# 1608_-_1.net
KiCad netlist of a schematic drawn in Altium Designer
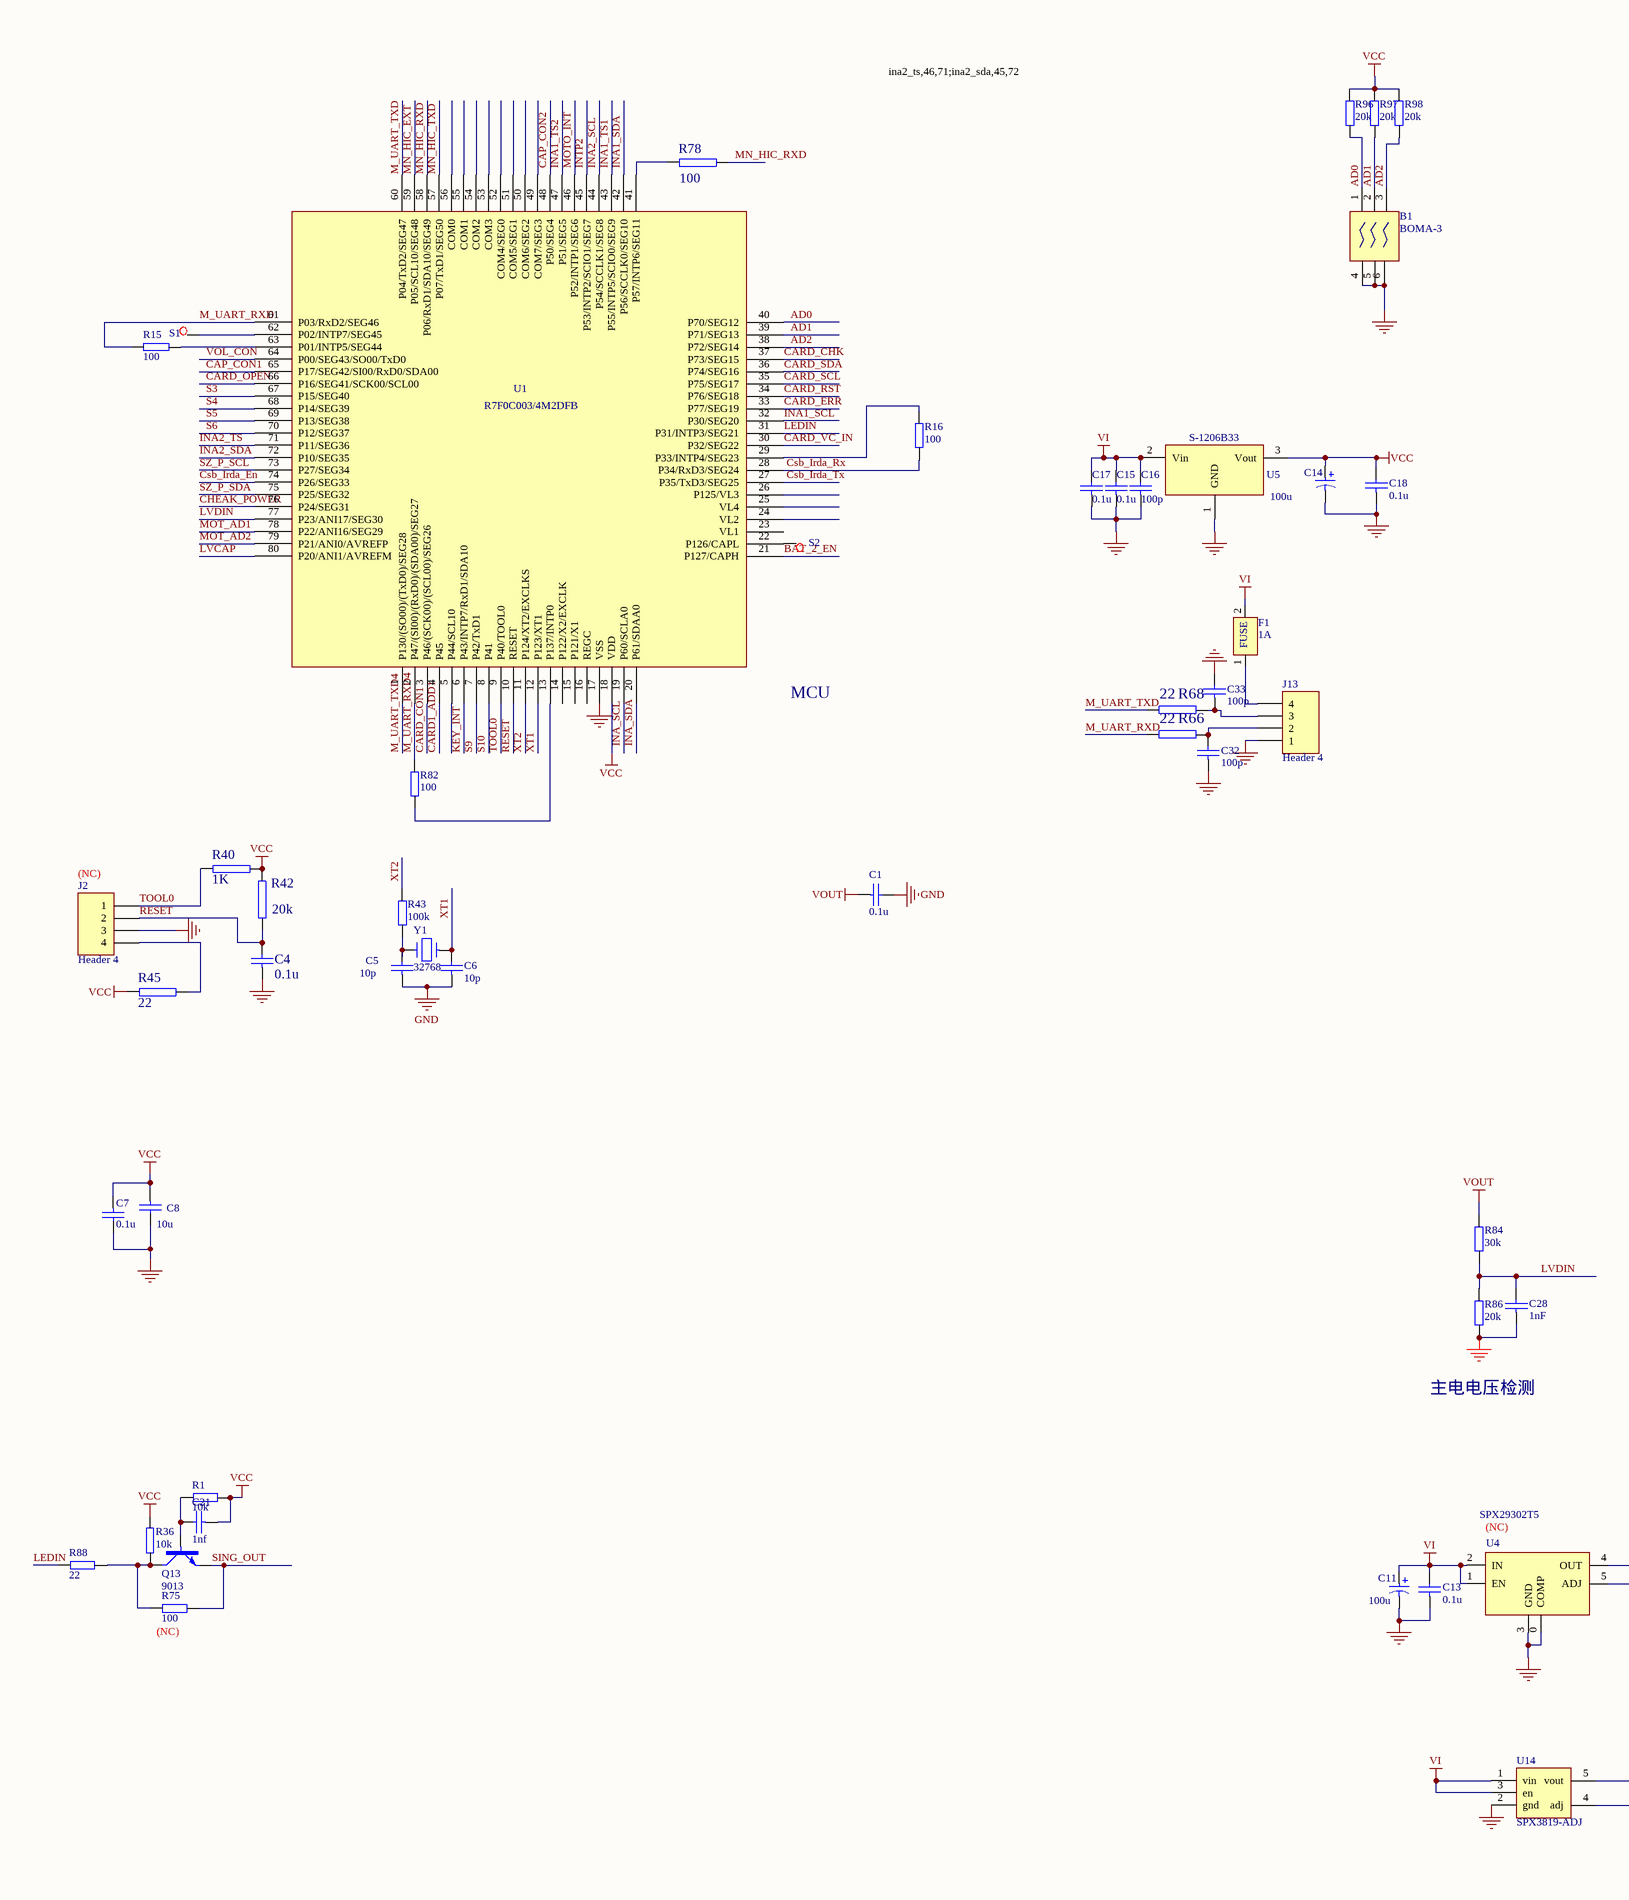
[diagram p0: 1608卡-原理图1.SchDoc, left]
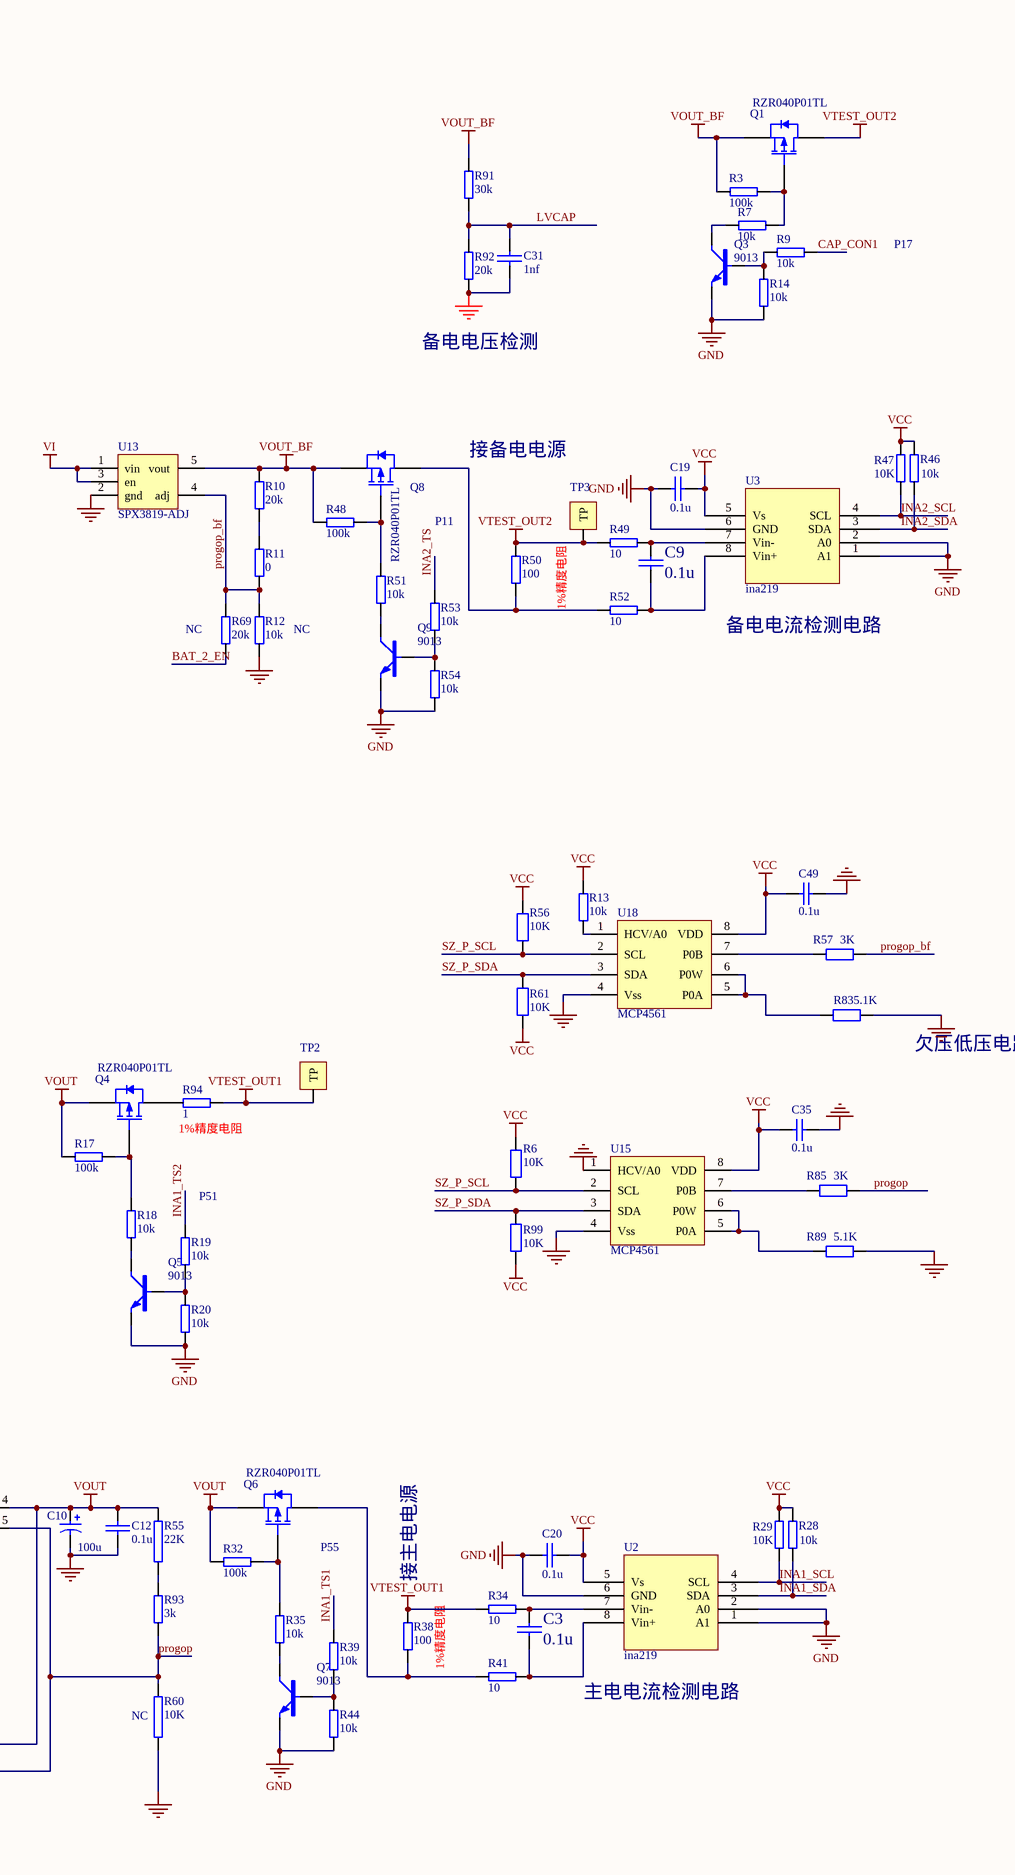
[diagram p1: 1608卡-原理图1.SchDoc, right]

(export (version "E")
  (design (tool "Eeschema 10.0.6"))
  (components
    (comp (ref "B1") (value "BOMA-3") (footprint "BOMA-3") (libsource (lib "chip") (part "BOMA-3")))
    (comp (ref "C1")
      (value "0.1u")
      (footprint "C0603")
      (description "无极性电容")
      (libsource (lib "CBB_Lib_SCH") (part "CAP"))
    )
    (comp (ref "C3") (value "0.1u") (footprint "C0603") (libsource (lib "*") (part "Pro28.tmp_UnNamed_45")))
    (comp (ref "C4")
      (value "0.1u")
      (footprint "C0603")
      (description "Capacitor")
      (libsource (lib "*") (part "CAP"))
    )
    (comp (ref "C5") (value "10p") (footprint "c0603") (libsource (lib "SCH_LIB_WX") (part "CAP1")))
    (comp (ref "C6") (value "10p") (footprint "c0603") (libsource (lib "SCH_LIB_WX") (part "CAP1")))
    (comp (ref "C7")
      (value "0.1u")
      (footprint "C0603")
      (description "无极性电容")
      (libsource (lib "CBB_Lib_SCH") (part "CAP"))
    )
    (comp (ref "C8")
      (value "10u")
      (footprint "C0603")
      (description "无极性电容")
      (libsource (lib "CBB_Lib_SCH") (part "CAP"))
    )
    (comp (ref "C9") (value "0.1u") (footprint "C0603") (libsource (lib "*") (part "Pro28.tmp_UnNamed_45")))
    (comp (ref "C10")
      (value "100u")
      (footprint "3528")
      (description "钽电容")
      (libsource (lib "CBB_Lib_SCH") (part "CAP-POL2"))
    )
    (comp (ref "C11")
      (value "100u")
      (footprint "3528")
      (description "钽电容")
      (libsource (lib "CBB_Lib_SCH") (part "CAP-POL2"))
    )
    (comp (ref "C12")
      (value "0.1u")
      (footprint "C0603")
      (description "无极性电容")
      (libsource (lib "CBB_Lib_SCH") (part "CAP"))
    )
    (comp (ref "C13")
      (value "0.1u")
      (footprint "C0603")
      (description "无极性电容")
      (libsource (lib "CBB_Lib_SCH") (part "CAP"))
    )
    (comp (ref "C14")
      (value "100u")
      (footprint "3528")
      (description "钽电容")
      (libsource (lib "CBB_Lib_SCH") (part "CAP-POL2"))
    )
    (comp (ref "C15")
      (value "0.1u")
      (footprint "C0603")
      (description "无极性电容")
      (libsource (lib "CBB_Lib_SCH") (part "CAP"))
    )
    (comp (ref "C16")
      (value "100p")
      (footprint "C0603")
      (description "无极性电容")
      (libsource (lib "CBB_Lib_SCH") (part "CAP"))
    )
    (comp (ref "C17")
      (value "0.1u")
      (footprint "C0603")
      (description "无极性电容")
      (libsource (lib "CBB_Lib_SCH") (part "CAP"))
    )
    (comp (ref "C18")
      (value "0.1u")
      (footprint "C0603")
      (description "无极性电容")
      (libsource (lib "CBB_Lib_SCH") (part "CAP"))
    )
    (comp (ref "C19")
      (value "0.1u")
      (footprint "C0603")
      (description "无极性电容")
      (libsource (lib "CBB_Lib_SCH") (part "CAP"))
    )
    (comp (ref "C20")
      (value "0.1u")
      (footprint "C0603")
      (description "无极性电容")
      (libsource (lib "CBB_Lib_SCH") (part "CAP"))
    )
    (comp (ref "C21")
      (value "1nf")
      (footprint "C0603")
      (description "无极性电容")
      (libsource (lib "CBB_Lib_SCH") (part "CAP"))
    )
    (comp (ref "C28")
      (value "1nF")
      (footprint "C0603")
      (description "无极性电容")
      (libsource (lib "CBB_Lib_SCH") (part "CAP"))
    )
    (comp (ref "C31")
      (value "1nf")
      (footprint "C0603")
      (description "无极性电容")
      (libsource (lib "CBB_Lib_SCH") (part "CAP"))
    )
    (comp (ref "C32")
      (value "100p")
      (footprint "C0603")
      (description "无极性电容")
      (libsource (lib "CBB_Lib_SCH") (part "CAP"))
    )
    (comp (ref "C33")
      (value "100p")
      (footprint "C0603")
      (description "无极性电容")
      (libsource (lib "CBB_Lib_SCH") (part "CAP"))
    )
    (comp (ref "C35")
      (value "0.1u")
      (footprint "c0603")
      (description "Capacitor")
      (fields (field (name "PUBLISHER") "Altium Limited"))
      (libsource (lib "Miscellaneous Devices") (part "Cap"))
    )
    (comp (ref "C49")
      (value "0.1u")
      (footprint "c0603")
      (description "Capacitor")
      (fields (field (name "PUBLISHER") "Altium Limited"))
      (libsource (lib "Miscellaneous Devices") (part "Cap"))
    )
    (comp (ref "F1") (value "1A") (footprint "R1206") (libsource (lib "chip") (part "FUSE")))
    (comp (ref "J2")
      (value "Header 4")
      (footprint "HDR1X4")
      (description "Header, 4-Pin")
      (fields (field (name "PUBLISHER") "Altium Limited"))
      (libsource (lib "") (part "Header 4_1"))
    )
    (comp (ref "J13")
      (value "Header 4")
      (footprint "HDX4")
      (description "Header, 4-Pin")
      (fields (field (name "PUBLISHER") "Altium Limited"))
      (libsource (lib "Miscellaneous Connectors") (part "Header 4"))
    )
    (comp (ref "Q1")
      (value "RZR040P01TL")
      (footprint "SOT-23-MOS")
      (description "P-channel  MOSFET")
      (libsource (lib "CBB_Lib_SCH") (part "MOS-P"))
    )
    (comp (ref "Q3")
      (value "9013")
      (footprint "SOT-23-TRAN")
      (description "NPN Transistor")
      (libsource (lib "CBB_Lib_SCH") (part "NPN-S"))
    )
    (comp (ref "Q4")
      (value "RZR040P01TL")
      (footprint "SOT-23-MOS")
      (description "P-channel  MOSFET")
      (libsource (lib "CBB_Lib_SCH") (part "MOS-P"))
    )
    (comp (ref "Q5")
      (value "9013")
      (footprint "SOT-23-TRAN")
      (description "NPN Transistor")
      (libsource (lib "CBB_Lib_SCH") (part "NPN-S"))
    )
    (comp (ref "Q6")
      (value "RZR040P01TL")
      (footprint "SOT-23-MOS")
      (description "P-channel  MOSFET")
      (libsource (lib "CBB_Lib_SCH") (part "MOS-P"))
    )
    (comp (ref "Q7")
      (value "9013")
      (footprint "SOT-23-TRAN")
      (description "NPN Transistor")
      (libsource (lib "CBB_Lib_SCH") (part "NPN-S"))
    )
    (comp (ref "Q8")
      (value "RZR040P01TL")
      (footprint "SOT-23-MOS")
      (description "P-channel  MOSFET")
      (libsource (lib "CBB_Lib_SCH") (part "MOS-P"))
    )
    (comp (ref "Q9")
      (value "9013")
      (footprint "SOT-23-TRAN")
      (description "NPN Transistor")
      (libsource (lib "CBB_Lib_SCH") (part "NPN-S"))
    )
    (comp (ref "Q13")
      (value "9013")
      (footprint "CBB_Lib_PCB:SOT-23-TRAN")
      (description "NPN Transistor")
      (libsource (lib "CBB_Lib_SCH") (part "NPN-S"))
    )
    (comp (ref "R1") (value "10k") (footprint "R0603") (libsource (lib "CBB_linshi_SCH") (part "RES  PASS")))
    (comp (ref "R3") (value "100k") (footprint "R0603") (libsource (lib "CBB_Lib_SCH") (part "RES")))
    (comp (ref "R6")
      (value "10K")
      (footprint "R0603")
      (description "Resistor")
      (fields (field (name "PUBLISHER") "Altium Limited"))
      (libsource (lib "Miscellaneous Devices") (part "Res2"))
    )
    (comp (ref "R7") (value "10k") (footprint "R0603") (libsource (lib "CBB_Lib_SCH") (part "RES")))
    (comp (ref "R9") (value "10k") (footprint "R0603") (libsource (lib "CBB_Lib_SCH") (part "RES")))
    (comp (ref "R10") (value "20k") (footprint "R0603") (libsource (lib "CBB_Lib_SCH") (part "RES")))
    (comp (ref "R11") (value "0") (footprint "R0603") (libsource (lib "CBB_Lib_SCH") (part "RES")))
    (comp (ref "R12") (value "10k") (footprint "R0603") (libsource (lib "CBB_Lib_SCH") (part "RES")))
    (comp (ref "R13") (value "10k") (footprint "R0603") (libsource (lib "CBB_Lib_SCH") (part "RES")))
    (comp (ref "R14") (value "10k") (footprint "R0603") (libsource (lib "CBB_Lib_SCH") (part "RES")))
    (comp (ref "R15") (value "100") (footprint "r0603") (libsource (lib "SCH_LIB_WX") (part "RES")))
    (comp (ref "R16") (value "100") (footprint "R0603") (libsource (lib "Devices") (part "RES")))
    (comp (ref "R17") (value "100k") (footprint "R0603") (libsource (lib "CBB_Lib_SCH") (part "RES")))
    (comp (ref "R18") (value "10k") (footprint "R0603") (libsource (lib "CBB_Lib_SCH") (part "RES")))
    (comp (ref "R19") (value "10k") (footprint "R0603") (libsource (lib "CBB_Lib_SCH") (part "RES")))
    (comp (ref "R20") (value "10k") (footprint "R0603") (libsource (lib "CBB_Lib_SCH") (part "RES")))
    (comp (ref "R28") (value "10k") (footprint "R0603") (libsource (lib "Int_Lib_WX") (part "RES")))
    (comp (ref "R29") (value "10K") (footprint "R0603") (libsource (lib "Int_Lib_WX") (part "RES")))
    (comp (ref "R32") (value "100k") (footprint "R0603") (libsource (lib "CBB_Lib_SCH") (part "RES")))
    (comp (ref "R34") (value "10") (footprint "R0603") (libsource (lib "CBB_Lib_SCH") (part "RES")))
    (comp (ref "R35") (value "10k") (footprint "R0603") (libsource (lib "CBB_Lib_SCH") (part "RES")))
    (comp (ref "R36") (value "10k") (footprint "R0603") (libsource (lib "CBB_linshi_SCH") (part "RES  PASS")))
    (comp (ref "R38") (value "100") (footprint "R1206") (libsource (lib "CBB_Lib_SCH") (part "RES")))
    (comp (ref "R39") (value "10k") (footprint "R0603") (libsource (lib "CBB_Lib_SCH") (part "RES")))
    (comp (ref "R40") (value "1K") (footprint "R0603") (libsource (lib "*") (part "RES11")))
    (comp (ref "R41") (value "10") (footprint "R0603") (libsource (lib "CBB_Lib_SCH") (part "RES")))
    (comp (ref "R42") (value "20k") (footprint "R0603") (libsource (lib "*") (part "RES11")))
    (comp (ref "R43") (value "100k") (footprint "r0603") (libsource (lib "SCH_LIB_WX") (part "RES")))
    (comp (ref "R44") (value "10k") (footprint "R0603") (libsource (lib "CBB_Lib_SCH") (part "RES")))
    (comp (ref "R45") (value "22") (footprint "R0603") (libsource (lib "*") (part "RES11")))
    (comp (ref "R46") (value "10k") (footprint "R0603") (libsource (lib "Int_Lib_WX") (part "RES")))
    (comp (ref "R47") (value "10K") (footprint "R0603") (libsource (lib "Int_Lib_WX") (part "RES")))
    (comp (ref "R48") (value "100k") (footprint "R0603") (libsource (lib "CBB_Lib_SCH") (part "RES")))
    (comp (ref "R49") (value "10") (footprint "R0603") (libsource (lib "CBB_Lib_SCH") (part "RES")))
    (comp (ref "R50") (value "100") (footprint "R1206") (libsource (lib "CBB_Lib_SCH") (part "RES")))
    (comp (ref "R51") (value "10k") (footprint "R0603") (libsource (lib "CBB_Lib_SCH") (part "RES")))
    (comp (ref "R52") (value "10") (footprint "R0603") (libsource (lib "CBB_Lib_SCH") (part "RES")))
    (comp (ref "R53") (value "10k") (footprint "R0603") (libsource (lib "CBB_Lib_SCH") (part "RES")))
    (comp (ref "R54") (value "10k") (footprint "R0603") (libsource (lib "CBB_Lib_SCH") (part "RES")))
    (comp (ref "R55") (value "22K") (footprint "R0603") (libsource (lib "*") (part "RES2")))
    (comp (ref "R56")
      (value "10K")
      (footprint "R0603")
      (description "Resistor")
      (fields (field (name "PUBLISHER") "Altium Limited"))
      (libsource (lib "Miscellaneous Devices") (part "Res2"))
    )
    (comp (ref "R57")
      (value "3K")
      (footprint "R0603")
      (description "Resistor")
      (fields (field (name "PUBLISHER") "Altium Limited"))
      (libsource (lib "") (part "Res2_1"))
    )
    (comp (ref "R60") (value "10K") (footprint "R0603") (libsource (lib "*") (part "RES2")))
    (comp (ref "R61")
      (value "10K")
      (footprint "R0603")
      (description "Resistor")
      (fields (field (name "PUBLISHER") "Altium Limited"))
      (libsource (lib "Miscellaneous Devices") (part "Res2"))
    )
    (comp (ref "R66") (value "22") (footprint "R0603") (libsource (lib "PCB_Project1_1") (part "RES2")))
    (comp (ref "R68") (value "22") (footprint "R0603") (libsource (lib "PCB_Project1_1") (part "RES2")))
    (comp (ref "R69") (value "20k") (footprint "R0603") (libsource (lib "CBB_Lib_SCH") (part "RES")))
    (comp (ref "R75") (value "100") (footprint "R0603") (libsource (lib "") (part "RES  PASS_1")))
    (comp (ref "R78") (value "100") (footprint "R0603") (libsource (lib "*") (part "RES11")))
    (comp (ref "R82") (value "100") (footprint "R0603") (libsource (lib "Devices") (part "RES")))
    (comp (ref "R83")
      (value "5.1K")
      (footprint "R0603")
      (description "Resistor")
      (fields (field (name "PUBLISHER") "Altium Limited"))
      (libsource (lib "") (part "Res2_1"))
    )
    (comp (ref "R84") (value "30k") (footprint "R0603") (libsource (lib "CBB_Lib_SCH") (part "RES")))
    (comp (ref "R85")
      (value "3K")
      (footprint "R0603")
      (description "Resistor")
      (fields (field (name "PUBLISHER") "Altium Limited"))
      (libsource (lib "") (part "Res2_1"))
    )
    (comp (ref "R86") (value "20k") (footprint "R0603") (libsource (lib "CBB_Lib_SCH") (part "RES")))
    (comp (ref "R88") (value "22") (footprint "R0603") (libsource (lib "CBB_linshi_SCH") (part "RES  PASS")))
    (comp (ref "R89")
      (value "5.1K")
      (footprint "R0603")
      (description "Resistor")
      (fields (field (name "PUBLISHER") "Altium Limited"))
      (libsource (lib "") (part "Res2_1"))
    )
    (comp (ref "R91") (value "30k") (footprint "R0603") (libsource (lib "CBB_Lib_SCH") (part "RES")))
    (comp (ref "R92") (value "20k") (footprint "R0603") (libsource (lib "CBB_Lib_SCH") (part "RES")))
    (comp (ref "R93") (value "3k") (footprint "R0603") (libsource (lib "CBB_Lib_SCH") (part "RES")))
    (comp (ref "R94") (value "1") (footprint "R1206") (libsource (lib "CBB_Lib_SCH") (part "RES")))
    (comp (ref "R96") (value "20k") (footprint "R0603") (libsource (lib "CBB_Lib_SCH") (part "RES")))
    (comp (ref "R97") (value "20k") (footprint "R0603") (libsource (lib "CBB_Lib_SCH") (part "RES")))
    (comp (ref "R98") (value "20k") (footprint "R0603") (libsource (lib "CBB_Lib_SCH") (part "RES")))
    (comp (ref "R99")
      (value "10K")
      (footprint "R0603")
      (description "Resistor")
      (fields (field (name "PUBLISHER") "Altium Limited"))
      (libsource (lib "Miscellaneous Devices") (part "Res2"))
    )
    (comp (ref "S1")
      (value "Test Point  PASS")
      (footprint "TP_S")
      (description "测试点")
      (libsource (lib "CBB_Lib_SCH") (part "Test Point  PASS"))
    )
    (comp (ref "S2")
      (value "Test Point  PASS")
      (footprint "TP_S")
      (description "测试点")
      (libsource (lib "CBB_Lib_SCH") (part "Test Point  PASS"))
    )
    (comp (ref "TP2") (value "TP") (footprint "TEST_PAD") (libsource (lib "chip") (part "TP")))
    (comp (ref "TP3") (value "TP") (footprint "TEST_PAD") (libsource (lib "chip") (part "TP")))
    (comp (ref "U1")
      (value "R7F0C003/4M2DFB")
      (footprint "MSP437QFP80")
      (libsource (lib "Schlib1") (part "R7F0C003/4M2DFB"))
    )
    (comp (ref "U2") (value "ina219") (footprint "SO-8") (libsource (lib "Schlib1") (part "Component_2")))
    (comp (ref "U3") (value "ina219") (footprint "SO-8") (libsource (lib "Schlib1") (part "Component_2")))
    (comp (ref "U4")
      (value "SPX29302T5")
      (footprint "TO-263-5")
      (fields (field (name "PUBLISHER") "Altium Limited"))
      (libsource (lib "SCH_LIB_WX") (part "SPX29302T5"))
    )
    (comp (ref "U5") (value "S-1206B33") (footprint "SOT-89") (libsource (lib "*") (part "VOLTRER1")))
    (comp (ref "U13")
      (value "SPX3819-ADJ")
      (footprint "SOT23-5")
      (libsource (lib "chip") (part "SPX3819-ADJ"))
    )
    (comp (ref "U14")
      (value "SPX3819-ADJ")
      (footprint "SOT23-5")
      (libsource (lib "chip") (part "SPX3819-ADJ"))
    )
    (comp (ref "U15") (value "MCP4561") (footprint "MSOP") (libsource (lib "ultra") (part "MCP4561")))
    (comp (ref "U18") (value "MCP4561") (footprint "MSOP") (libsource (lib "ultra") (part "MCP4561")))
    (comp (ref "Y1")
      (value "32768")
      (footprint "XTAL-2S")
      (description "晶振,2PIN")
      (libsource (lib "CBB_Lib_SCH") (part "XTAL1"))
    )
  )
  (nets
    (net (code "1") (name "/AD0") (class "Default")
      (node (ref "B1") (pin "1") (pinfunction "vout_1") (pintype "passive"))
      (node (ref "R96") (pin "1") (pintype "passive"))
      (node (ref "U1") (pin "40") (pinfunction "P70/SEG12_40") (pintype "passive"))
    )
    (net (code "2") (name "/AD1") (class "Default")
      (node (ref "B1") (pin "2") (pinfunction "vout_2") (pintype "passive"))
      (node (ref "R97") (pin "1") (pintype "passive"))
      (node (ref "U1") (pin "39") (pinfunction "P71/SEG13_39") (pintype "passive"))
    )
    (net (code "3") (name "/AD2") (class "Default")
      (node (ref "B1") (pin "3") (pinfunction "vout_3") (pintype "passive"))
      (node (ref "R98") (pin "1") (pintype "passive"))
      (node (ref "U1") (pin "38") (pinfunction "P72/SEG14_38") (pintype "passive"))
    )
    (net (code "4") (name "/BAT_2_EN") (class "Default")
      (node (ref "R69") (pin "2") (pintype "passive"))
      (node (ref "U1") (pin "21") (pinfunction "P127/CAPH_21") (pintype "passive"))
    )
    (net (code "5") (name "/CAP_CON1") (class "Default")
      (node (ref "R9") (pin "2") (pintype "passive"))
      (node (ref "U1") (pin "65") (pinfunction "P17/SEG42/SI00/RxD0/SDA00_65") (pintype "passive"))
    )
    (net (code "6") (name "/CAP_CON2") (class "Default")
      (node (ref "U1") (pin "48") (pinfunction "P50/SEG4_48") (pintype "passive"))
    )
    (net (code "7") (name "/CARD1_ADD1") (class "Default")
      (node (ref "U1") (pin "4") (pinfunction "P45_4") (pintype "passive"))
    )
    (net (code "8") (name "/CARD_CHK") (class "Default")
      (node (ref "U1") (pin "37") (pinfunction "P73/SEG15_37") (pintype "passive"))
    )
    (net (code "9") (name "/CARD_CON1") (class "Default")
      (node (ref "U1") (pin "3") (pinfunction "P46/(SCK00)/(SCL00)/SEG26_3") (pintype "passive"))
    )
    (net (code "10") (name "/CARD_ERR") (class "Default")
      (node (ref "U1") (pin "33") (pinfunction "P77/SEG19_33") (pintype "passive"))
    )
    (net (code "11") (name "/CARD_OPEN") (class "Default")
      (node (ref "U1") (pin "66") (pinfunction "P16/SEG41/SCK00/SCL00_66") (pintype "passive"))
    )
    (net (code "12") (name "/CARD_RST") (class "Default")
      (node (ref "U1") (pin "34") (pinfunction "P76/SEG18_34") (pintype "passive"))
    )
    (net (code "13") (name "/CARD_SCL") (class "Default")
      (node (ref "U1") (pin "35") (pinfunction "P75/SEG17_35") (pintype "passive"))
    )
    (net (code "14") (name "/CARD_SDA") (class "Default")
      (node (ref "U1") (pin "36") (pinfunction "P74/SEG16_36") (pintype "passive"))
    )
    (net (code "15") (name "/CARD_VC_IN") (class "Default")
      (node (ref "U1") (pin "30") (pinfunction "P32/SEG22_30") (pintype "passive"))
    )
    (net (code "16") (name "/CHEAK_POWER") (class "Default")
      (node (ref "U1") (pin "76") (pinfunction "P24/SEG31_76") (pintype "passive"))
    )
    (net (code "17") (name "/Csb_Irda_En") (class "Default")
      (node (ref "U1") (pin "74") (pinfunction "P26/SEG33_74") (pintype "passive"))
    )
    (net (code "18") (name "/Csb_Irda_Rx") (class "Default")
      (node (ref "R16") (pin "1") (pintype "passive"))
      (node (ref "U1") (pin "28") (pinfunction "P34/RxD3/SEG24_28") (pintype "passive"))
    )
    (net (code "19") (name "/Csb_Irda_Tx") (class "Default")
      (node (ref "U1") (pin "27") (pinfunction "P35/TxD3/SEG25_27") (pintype "passive"))
    )
    (net (code "20") (name "/INA1_SCL") (class "Default")
      (node (ref "R29") (pin "1") (pintype "passive"))
      (node (ref "U1") (pin "32") (pinfunction "P30/SEG20_32") (pintype "passive"))
      (node (ref "U2") (pin "4") (pinfunction "SCL_4") (pintype "passive"))
    )
    (net (code "21") (name "/INA1_SDA") (class "Default")
      (node (ref "R28") (pin "1") (pintype "passive"))
      (node (ref "U1") (pin "42") (pinfunction "P56/SCCLK0/SEG10_42") (pintype "passive"))
      (node (ref "U2") (pin "3") (pinfunction "SDA_3") (pintype "passive"))
    )
    (net (code "22") (name "/INA1_TS1") (class "Default")
      (node (ref "R39") (pin "2") (pintype "passive"))
      (node (ref "U1") (pin "43") (pinfunction "P55/INTP5/SCIO0/SEG9_43") (pintype "passive"))
    )
    (net (code "23") (name "/INA1_TS2") (class "Default")
      (node (ref "R19") (pin "2") (pintype "passive"))
      (node (ref "U1") (pin "47") (pinfunction "P51/SEG5_47") (pintype "passive"))
    )
    (net (code "24") (name "/INA2_SCL") (class "Default")
      (node (ref "R47") (pin "1") (pintype "passive"))
      (node (ref "U1") (pin "44") (pinfunction "P54/SCCLK1/SEG8_44") (pintype "passive"))
      (node (ref "U3") (pin "4") (pinfunction "SCL_4") (pintype "passive"))
    )
    (net (code "25") (name "/INA2_SDA") (class "Default")
      (node (ref "R46") (pin "1") (pintype "passive"))
      (node (ref "U1") (pin "72") (pinfunction "P10/SEG35_72") (pintype "passive"))
      (node (ref "U3") (pin "3") (pinfunction "SDA_3") (pintype "passive"))
    )
    (net (code "26") (name "/INA2_TS") (class "Default")
      (node (ref "R53") (pin "2") (pintype "passive"))
      (node (ref "U1") (pin "71") (pinfunction "P11/SEG36_71") (pintype "passive"))
    )
    (net (code "27") (name "/INA_SCL") (class "Default")
      (node (ref "U1") (pin "19") (pinfunction "P60/SCLA0_19") (pintype "passive"))
    )
    (net (code "28") (name "/INA_SDA") (class "Default")
      (node (ref "U1") (pin "20") (pinfunction "P61/SDAA0_20") (pintype "passive"))
    )
    (net (code "29") (name "/INTP2") (class "Default")
      (node (ref "U1") (pin "45") (pinfunction "P53/INTP2/SCIO1/SEG7_45") (pintype "passive"))
    )
    (net (code "30") (name "/KEY_INT") (class "Default")
      (node (ref "U1") (pin "6") (pinfunction "P43/INTP7/RxD1/SDA10_6") (pintype "passive"))
    )
    (net (code "31") (name "/LEDIN") (class "Default")
      (node (ref "R88") (pin "1") (pintype "passive"))
      (node (ref "U1") (pin "31") (pinfunction "P31/INTP3/SEG21_31") (pintype "passive"))
    )
    (net (code "32") (name "/LVCAP") (class "Default")
      (node (ref "C31") (pin "2") (pintype "passive"))
      (node (ref "R91") (pin "2") (pintype "passive"))
      (node (ref "R92") (pin "1") (pintype "passive"))
      (node (ref "U1") (pin "80") (pinfunction "P20/ANI1/AVREFM_80") (pintype "passive"))
    )
    (net (code "33") (name "/LVDIN") (class "Default")
      (node (ref "C28") (pin "2") (pintype "passive"))
      (node (ref "R84") (pin "2") (pintype "passive"))
      (node (ref "R86") (pin "1") (pintype "passive"))
      (node (ref "U1") (pin "77") (pinfunction "P23/ANI17/SEG30_77") (pintype "passive"))
    )
    (net (code "34") (name "/MN_HIC_EXT") (class "Default")
      (node (ref "U1") (pin "59") (pinfunction "P05/SCL10/SEG48_59") (pintype "passive"))
    )
    (net (code "35") (name "/MN_HIC_RXD") (class "Default")
      (node (ref "R78") (pin "2") (pinfunction "2_2") (pintype "passive"))
      (node (ref "U1") (pin "58") (pinfunction "P06/RxD1/SDA10/SEG49_58") (pintype "passive"))
    )
    (net (code "36") (name "/MN_HIC_TXD") (class "Default")
      (node (ref "U1") (pin "57") (pinfunction "P07/TxD1/SEG50_57") (pintype "passive"))
    )
    (net (code "37") (name "/MOTO_INT") (class "Default")
      (node (ref "U1") (pin "46") (pinfunction "P52/INTP1/SEG6_46") (pintype "passive"))
    )
    (net (code "38") (name "/MOT_AD1") (class "Default")
      (node (ref "U1") (pin "78") (pinfunction "P22/ANI16/SEG29_78") (pintype "passive"))
    )
    (net (code "39") (name "/MOT_AD2") (class "Default")
      (node (ref "U1") (pin "79") (pinfunction "P21/ANI0/AVREFP_79") (pintype "passive"))
    )
    (net (code "40") (name "/M_UART_RXD") (class "Default")
      (node (ref "R15") (pin "2") (pintype "passive"))
      (node (ref "R66") (pin "2") (pinfunction "2_2") (pintype "passive"))
      (node (ref "U1") (pin "61") (pinfunction "P03/RxD2/SEG46_61") (pintype "passive"))
    )
    (net (code "41") (name "/M_UART_RXD4") (class "Default")
      (node (ref "R82") (pin "2") (pintype "passive"))
      (node (ref "U1") (pin "2") (pinfunction "P47/(SI00)/(RxD0)/(SDA00)/SEG27_2") (pintype "passive"))
    )
    (net (code "42") (name "/M_UART_TXD") (class "Default")
      (node (ref "R68") (pin "2") (pinfunction "2_2") (pintype "passive"))
      (node (ref "U1") (pin "60") (pinfunction "P04/TxD2/SEG47_60") (pintype "passive"))
    )
    (net (code "43") (name "/M_UART_TXD4") (class "Default")
      (node (ref "U1") (pin "1") (pinfunction "P130/(SO00)/(TxD0)/SEG28_1") (pintype "passive"))
    )
    (net (code "44") (name "/RESET") (class "Default")
      (node (ref "C4") (pin "2") (pinfunction "2_2") (pintype "passive"))
      (node (ref "J2") (pin "2") (pinfunction "2_2") (pintype "passive"))
      (node (ref "R42") (pin "2") (pinfunction "2_2") (pintype "passive"))
      (node (ref "U1") (pin "10") (pinfunction "RESET_10") (pintype "passive"))
    )
    (net (code "45") (name "/S3") (class "Default")
      (node (ref "U1") (pin "67") (pinfunction "P15/SEG40_67") (pintype "passive"))
    )
    (net (code "46") (name "/S4") (class "Default")
      (node (ref "U1") (pin "68") (pinfunction "P14/SEG39_68") (pintype "passive"))
    )
    (net (code "47") (name "/S5") (class "Default")
      (node (ref "U1") (pin "69") (pinfunction "P13/SEG38_69") (pintype "passive"))
    )
    (net (code "48") (name "/S6") (class "Default")
      (node (ref "U1") (pin "70") (pinfunction "P12/SEG37_70") (pintype "passive"))
    )
    (net (code "49") (name "/S9") (class "Default")
      (node (ref "U1") (pin "7") (pinfunction "P42/TxD1_7") (pintype "passive"))
    )
    (net (code "50") (name "/S10") (class "Default")
      (node (ref "U1") (pin "8") (pinfunction "P41_8") (pintype "passive"))
    )
    (net (code "51") (name "/SING_OUT") (class "Default")
      (node (ref "Q13") (pin "E") (pinfunction "E_E") (pintype "passive"))
      (node (ref "R75") (pin "1") (pintype "passive"))
    )
    (net (code "52") (name "/SZ_P_SCL") (class "Default")
      (node (ref "R56") (pin "2") (pinfunction "2_2") (pintype "passive"))
      (node (ref "R6") (pin "2") (pinfunction "2_2") (pintype "passive"))
      (node (ref "U1") (pin "73") (pinfunction "P27/SEG34_73") (pintype "passive"))
      (node (ref "U15") (pin "2") (pinfunction "SCL_2") (pintype "passive"))
      (node (ref "U18") (pin "2") (pinfunction "SCL_2") (pintype "passive"))
    )
    (net (code "53") (name "/SZ_P_SDA") (class "Default")
      (node (ref "R61") (pin "1") (pinfunction "1_1") (pintype "passive"))
      (node (ref "R99") (pin "1") (pinfunction "1_1") (pintype "passive"))
      (node (ref "U1") (pin "75") (pinfunction "P25/SEG32_75") (pintype "passive"))
      (node (ref "U15") (pin "3") (pinfunction "SDA_3") (pintype "passive"))
      (node (ref "U18") (pin "3") (pinfunction "SDA_3") (pintype "passive"))
    )
    (net (code "54") (name "/TOOL0") (class "Default")
      (node (ref "J2") (pin "1") (pinfunction "1_1") (pintype "passive"))
      (node (ref "R40") (pin "1") (pinfunction "1_1") (pintype "passive"))
      (node (ref "U1") (pin "9") (pinfunction "P40/TOOL0_9") (pintype "passive"))
    )
    (net (code "55") (name "/VOL_CON") (class "Default")
      (node (ref "U1") (pin "64") (pinfunction "P00/SEG43/SO00/TxD0_64") (pintype "passive"))
    )
    (net (code "56") (name "/XT1") (class "Default")
      (node (ref "C6") (pin "2") (pintype "passive"))
      (node (ref "U1") (pin "12") (pinfunction "P123/XT1_12") (pintype "passive"))
      (node (ref "Y1") (pin "1") (pinfunction "1_1") (pintype "passive"))
    )
    (net (code "57") (name "/XT2") (class "Default")
      (node (ref "R43") (pin "2") (pintype "passive"))
      (node (ref "U1") (pin "11") (pinfunction "P124/XT2/EXCLKS_11") (pintype "passive"))
    )
    (net (code "58") (name "/progop") (class "Default")
      (node (ref "R60") (pin "1") (pintype "passive"))
      (node (ref "R85") (pin "1") (pinfunction "1_1") (pintype "passive"))
      (node (ref "R93") (pin "2") (pintype "passive"))
      (node (ref "U14") (pin "4") (pinfunction "adj_4") (pintype "passive"))
      (node (ref "U4") (pin "5") (pinfunction "ADJ_5") (pintype "passive"))
    )
    (net (code "59") (name "/progop_bf") (class "Default")
      (node (ref "R11") (pin "1") (pintype "passive"))
      (node (ref "R12") (pin "2") (pintype "passive"))
      (node (ref "R57") (pin "1") (pinfunction "1_1") (pintype "passive"))
      (node (ref "R69") (pin "1") (pintype "passive"))
      (node (ref "U13") (pin "4") (pinfunction "adj_4") (pintype "passive"))
    )
    (net (code "60") (name "GND") (class "Default")
      (node (ref "B1") (pin "4") (pinfunction "vout_4") (pintype "passive"))
      (node (ref "B1") (pin "5") (pinfunction "vout_5") (pintype "passive"))
      (node (ref "B1") (pin "6") (pinfunction "vout_6") (pintype "passive"))
      (node (ref "C1") (pin "2") (pintype "passive"))
      (node (ref "C10") (pin "2") (pinfunction "2_2") (pintype "passive"))
      (node (ref "C11") (pin "2") (pinfunction "2_2") (pintype "passive"))
      (node (ref "C12") (pin "1") (pintype "passive"))
      (node (ref "C13") (pin "1") (pintype "passive"))
      (node (ref "C14") (pin "2") (pinfunction "2_2") (pintype "passive"))
      (node (ref "C15") (pin "1") (pintype "passive"))
      (node (ref "C16") (pin "1") (pintype "passive"))
      (node (ref "C17") (pin "1") (pintype "passive"))
      (node (ref "C18") (pin "1") (pintype "passive"))
      (node (ref "C19") (pin "1") (pintype "passive"))
      (node (ref "C20") (pin "1") (pintype "passive"))
      (node (ref "C28") (pin "1") (pintype "passive"))
      (node (ref "C31") (pin "1") (pintype "passive"))
      (node (ref "C32") (pin "1") (pintype "passive"))
      (node (ref "C33") (pin "2") (pintype "passive"))
      (node (ref "C35") (pin "2") (pinfunction "2_2") (pintype "passive"))
      (node (ref "C4") (pin "1") (pinfunction "1_1") (pintype "passive"))
      (node (ref "C49") (pin "2") (pinfunction "2_2") (pintype "passive"))
      (node (ref "C5") (pin "1") (pintype "passive"))
      (node (ref "C6") (pin "1") (pintype "passive"))
      (node (ref "C7") (pin "2") (pintype "passive"))
      (node (ref "C8") (pin "2") (pintype "passive"))
      (node (ref "J13") (pin "1") (pinfunction "1_1") (pintype "passive"))
      (node (ref "J2") (pin "3") (pinfunction "3_3") (pintype "passive"))
      (node (ref "Q3") (pin "E") (pinfunction "E_E") (pintype "passive"))
      (node (ref "Q5") (pin "E") (pinfunction "E_E") (pintype "passive"))
      (node (ref "Q7") (pin "E") (pinfunction "E_E") (pintype "passive"))
      (node (ref "Q9") (pin "E") (pinfunction "E_E") (pintype "passive"))
      (node (ref "R12") (pin "1") (pintype "passive"))
      (node (ref "R14") (pin "2") (pintype "passive"))
      (node (ref "R20") (pin "2") (pintype "passive"))
      (node (ref "R44") (pin "2") (pintype "passive"))
      (node (ref "R54") (pin "2") (pintype "passive"))
      (node (ref "R60") (pin "2") (pintype "passive"))
      (node (ref "R83") (pin "1") (pinfunction "1_1") (pintype "passive"))
      (node (ref "R86") (pin "2") (pintype "passive"))
      (node (ref "R89") (pin "1") (pinfunction "1_1") (pintype "passive"))
      (node (ref "R92") (pin "2") (pintype "passive"))
      (node (ref "U1") (pin "17") (pinfunction "VSS_17") (pintype "passive"))
      (node (ref "U13") (pin "2") (pinfunction "gnd_2") (pintype "passive"))
      (node (ref "U14") (pin "2") (pinfunction "gnd_2") (pintype "passive"))
      (node (ref "U15") (pin "1") (pinfunction "HCV/A0_1") (pintype "passive"))
      (node (ref "U15") (pin "4") (pinfunction "Vss_4") (pintype "passive"))
      (node (ref "U18") (pin "4") (pinfunction "Vss_4") (pintype "passive"))
      (node (ref "U2") (pin "1") (pinfunction "A1_1") (pintype "passive"))
      (node (ref "U2") (pin "2") (pinfunction "A0_2") (pintype "passive"))
      (node (ref "U2") (pin "6") (pinfunction "GND_6") (pintype "passive"))
      (node (ref "U3") (pin "1") (pinfunction "A1_1") (pintype "passive"))
      (node (ref "U3") (pin "2") (pinfunction "A0_2") (pintype "passive"))
      (node (ref "U3") (pin "6") (pinfunction "GND_6") (pintype "passive"))
      (node (ref "U4") (pin "0") (pinfunction "COMP_0") (pintype "passive"))
      (node (ref "U4") (pin "3") (pinfunction "GND_3") (pintype "passive"))
      (node (ref "U5") (pin "1") (pinfunction "GND_1") (pintype "passive"))
    )
    (net (code "61") (name "Net-(C5-Pad2)") (class "Default")
      (node (ref "C5") (pin "2") (pintype "passive"))
      (node (ref "R43") (pin "1") (pintype "passive"))
      (node (ref "Y1") (pin "2") (pinfunction "2_2") (pintype "passive"))
    )
    (net (code "62") (name "Net-(C21-Pad2)") (class "Default")
      (node (ref "C21") (pin "2") (pintype "passive"))
      (node (ref "Q13") (pin "B") (pinfunction "B_B") (pintype "passive"))
      (node (ref "R1") (pin "1") (pintype "passive"))
    )
    (net (code "63") (name "Net-(C32-Pad2)") (class "Default")
      (node (ref "C32") (pin "2") (pintype "passive"))
      (node (ref "J13") (pin "2") (pinfunction "2_2") (pintype "passive"))
      (node (ref "R66") (pin "1") (pinfunction "1_1") (pintype "passive"))
    )
    (net (code "64") (name "Net-(C33-Pad1)") (class "Default")
      (node (ref "C33") (pin "1") (pintype "passive"))
      (node (ref "J13") (pin "3") (pinfunction "3_3") (pintype "passive"))
      (node (ref "R68") (pin "1") (pinfunction "1_1") (pintype "passive"))
    )
    (net (code "65") (name "Net-(F1-I-Pad1)") (class "Default")
      (node (ref "F1") (pin "1") (pinfunction "I_1") (pintype "passive"))
      (node (ref "J13") (pin "4") (pinfunction "4_4") (pintype "passive"))
    )
    (net (code "66") (name "Net-(J2-Pad4)") (class "Default")
      (node (ref "J2") (pin "4") (pinfunction "4_4") (pintype "passive"))
      (node (ref "R45") (pin "2") (pinfunction "2_2") (pintype "passive"))
    )
    (net (code "67") (name "Net-(Q1-PadG)") (class "Default")
      (node (ref "Q1") (pin "G") (pinfunction "G_G") (pintype "passive"))
      (node (ref "R3") (pin "1") (pintype "passive"))
      (node (ref "R7") (pin "2") (pintype "passive"))
    )
    (net (code "68") (name "Net-(Q3-PadB)") (class "Default")
      (node (ref "Q3") (pin "B") (pinfunction "B_B") (pintype "passive"))
      (node (ref "R14") (pin "1") (pintype "passive"))
      (node (ref "R9") (pin "1") (pintype "passive"))
    )
    (net (code "69") (name "Net-(Q3-PadC)") (class "Default")
      (node (ref "Q3") (pin "C") (pinfunction "C_C") (pintype "passive"))
      (node (ref "R7") (pin "1") (pintype "passive"))
    )
    (net (code "70") (name "Net-(Q4-PadD)") (class "Default")
      (node (ref "Q4") (pin "D") (pinfunction "D_D") (pintype "passive"))
      (node (ref "R94") (pin "2") (pintype "passive"))
    )
    (net (code "71") (name "Net-(Q4-PadG)") (class "Default")
      (node (ref "Q4") (pin "G") (pinfunction "G_G") (pintype "passive"))
      (node (ref "R17") (pin "1") (pintype "passive"))
      (node (ref "R18") (pin "2") (pintype "passive"))
    )
    (net (code "72") (name "Net-(Q5-PadB)") (class "Default")
      (node (ref "Q5") (pin "B") (pinfunction "B_B") (pintype "passive"))
      (node (ref "R19") (pin "1") (pintype "passive"))
      (node (ref "R20") (pin "1") (pintype "passive"))
    )
    (net (code "73") (name "Net-(Q5-PadC)") (class "Default")
      (node (ref "Q5") (pin "C") (pinfunction "C_C") (pintype "passive"))
      (node (ref "R18") (pin "1") (pintype "passive"))
    )
    (net (code "74") (name "Net-(Q6-PadD)") (class "Default")
      (node (ref "Q6") (pin "D") (pinfunction "D_D") (pintype "passive"))
      (node (ref "R38") (pin "2") (pintype "passive"))
      (node (ref "R41") (pin "2") (pintype "passive"))
    )
    (net (code "75") (name "Net-(Q6-PadG)") (class "Default")
      (node (ref "Q6") (pin "G") (pinfunction "G_G") (pintype "passive"))
      (node (ref "R32") (pin "1") (pintype "passive"))
      (node (ref "R35") (pin "2") (pintype "passive"))
    )
    (net (code "76") (name "Net-(Q7-PadB)") (class "Default")
      (node (ref "Q7") (pin "B") (pinfunction "B_B") (pintype "passive"))
      (node (ref "R39") (pin "1") (pintype "passive"))
      (node (ref "R44") (pin "1") (pintype "passive"))
    )
    (net (code "77") (name "Net-(Q7-PadC)") (class "Default")
      (node (ref "Q7") (pin "C") (pinfunction "C_C") (pintype "passive"))
      (node (ref "R35") (pin "1") (pintype "passive"))
    )
    (net (code "78") (name "Net-(Q8-PadD)") (class "Default")
      (node (ref "Q8") (pin "D") (pinfunction "D_D") (pintype "passive"))
      (node (ref "R50") (pin "2") (pintype "passive"))
      (node (ref "R52") (pin "2") (pintype "passive"))
    )
    (net (code "79") (name "Net-(Q8-PadG)") (class "Default")
      (node (ref "Q8") (pin "G") (pinfunction "G_G") (pintype "passive"))
      (node (ref "R48") (pin "1") (pintype "passive"))
      (node (ref "R51") (pin "2") (pintype "passive"))
    )
    (net (code "80") (name "Net-(Q9-PadB)") (class "Default")
      (node (ref "Q9") (pin "B") (pinfunction "B_B") (pintype "passive"))
      (node (ref "R53") (pin "1") (pintype "passive"))
      (node (ref "R54") (pin "1") (pintype "passive"))
    )
    (net (code "81") (name "Net-(Q9-PadC)") (class "Default")
      (node (ref "Q9") (pin "C") (pinfunction "C_C") (pintype "passive"))
      (node (ref "R51") (pin "1") (pintype "passive"))
    )
    (net (code "82") (name "Net-(Q13-PadC)") (class "Default")
      (node (ref "Q13") (pin "C") (pinfunction "C_C") (pintype "passive"))
      (node (ref "R36") (pin "1") (pintype "passive"))
      (node (ref "R75") (pin "2") (pintype "passive"))
      (node (ref "R88") (pin "2") (pintype "passive"))
    )
    (net (code "83") (name "Net-(R10-Pad1)") (class "Default")
      (node (ref "R10") (pin "1") (pintype "passive"))
      (node (ref "R11") (pin "2") (pintype "passive"))
    )
    (net (code "84") (name "Net-(R55-Pad2)") (class "Default")
      (node (ref "R55") (pin "2") (pintype "passive"))
      (node (ref "R93") (pin "1") (pintype "passive"))
    )
    (net (code "85") (name "Net-(U1-P01{slash}INTP5{slash}SEG44)") (class "Default")
      (node (ref "R15") (pin "1") (pintype "passive"))
      (node (ref "U1") (pin "63") (pinfunction "P01/INTP5/SEG44_63") (pintype "passive"))
    )
    (net (code "86") (name "Net-(U1-P02{slash}INTP7{slash}SEG45)") (class "Default")
      (node (ref "S1") (pin "1") (pinfunction "1_1") (pintype "passive"))
      (node (ref "U1") (pin "62") (pinfunction "P02/INTP7/SEG45_62") (pintype "passive"))
    )
    (net (code "87") (name "Net-(U1-P33{slash}INTP4{slash}SEG23)") (class "Default")
      (node (ref "R16") (pin "2") (pintype "passive"))
      (node (ref "U1") (pin "29") (pinfunction "P33/INTP4/SEG23_29") (pintype "passive"))
    )
    (net (code "88") (name "Net-(U1-P57{slash}INTP6{slash}SEG11)") (class "Default")
      (node (ref "R78") (pin "1") (pinfunction "1_1") (pintype "passive"))
      (node (ref "U1") (pin "41") (pinfunction "P57/INTP6/SEG11_41") (pintype "passive"))
    )
    (net (code "89") (name "Net-(U1-P126{slash}CAPL)") (class "Default")
      (node (ref "S2") (pin "1") (pinfunction "1_1") (pintype "passive"))
      (node (ref "U1") (pin "22") (pinfunction "P126/CAPL_22") (pintype "passive"))
    )
    (net (code "90") (name "Net-(U1-P137{slash}INTP0)") (class "Default")
      (node (ref "R82") (pin "1") (pintype "passive"))
      (node (ref "U1") (pin "13") (pinfunction "P137/INTP0_13") (pintype "passive"))
    )
    (net (code "91") (name "Net-(U2-Vin+)") (class "Default")
      (node (ref "C3") (pin "2") (pintype "passive"))
      (node (ref "R41") (pin "1") (pintype "passive"))
      (node (ref "U2") (pin "8") (pinfunction "Vin+_8") (pintype "passive"))
    )
    (net (code "92") (name "Net-(U2-Vin-)") (class "Default")
      (node (ref "C3") (pin "1") (pintype "passive"))
      (node (ref "R34") (pin "1") (pintype "passive"))
      (node (ref "U2") (pin "7") (pinfunction "Vin-_7") (pintype "passive"))
    )
    (net (code "93") (name "Net-(U3-Vin+)") (class "Default")
      (node (ref "C9") (pin "2") (pintype "passive"))
      (node (ref "R52") (pin "1") (pintype "passive"))
      (node (ref "U3") (pin "8") (pinfunction "Vin+_8") (pintype "passive"))
    )
    (net (code "94") (name "Net-(U3-Vin-)") (class "Default")
      (node (ref "C9") (pin "1") (pintype "passive"))
      (node (ref "R49") (pin "1") (pintype "passive"))
      (node (ref "U3") (pin "7") (pinfunction "Vin-_7") (pintype "passive"))
    )
    (net (code "95") (name "Net-(U15-P0A)") (class "Default")
      (node (ref "R89") (pin "2") (pinfunction "2_2") (pintype "passive"))
      (node (ref "U15") (pin "5") (pinfunction "P0A_5") (pintype "passive"))
      (node (ref "U15") (pin "6") (pinfunction "P0W_6") (pintype "passive"))
    )
    (net (code "96") (name "Net-(U15-P0B)") (class "Default")
      (node (ref "R85") (pin "2") (pinfunction "2_2") (pintype "passive"))
      (node (ref "U15") (pin "7") (pinfunction "P0B_7") (pintype "passive"))
    )
    (net (code "97") (name "Net-(U18-HCV{slash}A0)") (class "Default")
      (node (ref "R13") (pin "2") (pintype "passive"))
      (node (ref "U18") (pin "1") (pinfunction "HCV/A0_1") (pintype "passive"))
    )
    (net (code "98") (name "Net-(U18-P0A)") (class "Default")
      (node (ref "R83") (pin "2") (pinfunction "2_2") (pintype "passive"))
      (node (ref "U18") (pin "5") (pinfunction "P0A_5") (pintype "passive"))
      (node (ref "U18") (pin "6") (pinfunction "P0W_6") (pintype "passive"))
    )
    (net (code "99") (name "Net-(U18-P0B)") (class "Default")
      (node (ref "R57") (pin "2") (pinfunction "2_2") (pintype "passive"))
      (node (ref "U18") (pin "7") (pinfunction "P0B_7") (pintype "passive"))
    )
    (net (code "100") (name "VCC") (class "Default")
      (node (ref "C14") (pin "1") (pinfunction "1_1") (pintype "passive"))
      (node (ref "C18") (pin "2") (pintype "passive"))
      (node (ref "C19") (pin "2") (pintype "passive"))
      (node (ref "C20") (pin "2") (pintype "passive"))
      (node (ref "C21") (pin "1") (pintype "passive"))
      (node (ref "C35") (pin "1") (pinfunction "1_1") (pintype "passive"))
      (node (ref "C49") (pin "1") (pinfunction "1_1") (pintype "passive"))
      (node (ref "C7") (pin "1") (pintype "passive"))
      (node (ref "C8") (pin "1") (pintype "passive"))
      (node (ref "R1") (pin "2") (pintype "passive"))
      (node (ref "R13") (pin "1") (pintype "passive"))
      (node (ref "R28") (pin "2") (pintype "passive"))
      (node (ref "R29") (pin "2") (pintype "passive"))
      (node (ref "R36") (pin "2") (pintype "passive"))
      (node (ref "R40") (pin "2") (pinfunction "2_2") (pintype "passive"))
      (node (ref "R42") (pin "1") (pinfunction "1_1") (pintype "passive"))
      (node (ref "R45") (pin "1") (pinfunction "1_1") (pintype "passive"))
      (node (ref "R46") (pin "2") (pintype "passive"))
      (node (ref "R47") (pin "2") (pintype "passive"))
      (node (ref "R56") (pin "1") (pinfunction "1_1") (pintype "passive"))
      (node (ref "R6") (pin "1") (pinfunction "1_1") (pintype "passive"))
      (node (ref "R61") (pin "2") (pinfunction "2_2") (pintype "passive"))
      (node (ref "R96") (pin "2") (pintype "passive"))
      (node (ref "R97") (pin "2") (pintype "passive"))
      (node (ref "R98") (pin "2") (pintype "passive"))
      (node (ref "R99") (pin "2") (pinfunction "2_2") (pintype "passive"))
      (node (ref "U1") (pin "18") (pinfunction "VDD_18") (pintype "passive"))
      (node (ref "U15") (pin "8") (pinfunction "VDD_8") (pintype "passive"))
      (node (ref "U18") (pin "8") (pinfunction "VDD_8") (pintype "passive"))
      (node (ref "U2") (pin "5") (pinfunction "Vs_5") (pintype "passive"))
      (node (ref "U3") (pin "5") (pinfunction "Vs_5") (pintype "passive"))
      (node (ref "U5") (pin "3") (pinfunction "Vout_3") (pintype "passive"))
    )
    (net (code "101") (name "VI") (class "Default")
      (node (ref "C11") (pin "1") (pinfunction "1_1") (pintype "passive"))
      (node (ref "C13") (pin "2") (pintype "passive"))
      (node (ref "C15") (pin "2") (pintype "passive"))
      (node (ref "C16") (pin "2") (pintype "passive"))
      (node (ref "C17") (pin "2") (pintype "passive"))
      (node (ref "F1") (pin "2") (pinfunction "I_2") (pintype "passive"))
      (node (ref "U13") (pin "1") (pinfunction "vin_1") (pintype "passive"))
      (node (ref "U13") (pin "3") (pinfunction "en_3") (pintype "passive"))
      (node (ref "U14") (pin "1") (pinfunction "vin_1") (pintype "passive"))
      (node (ref "U14") (pin "3") (pinfunction "en_3") (pintype "passive"))
      (node (ref "U4") (pin "1") (pinfunction "EN_1") (pintype "passive"))
      (node (ref "U4") (pin "2") (pinfunction "IN_2") (pintype "passive"))
      (node (ref "U5") (pin "2") (pinfunction "Vin_2") (pintype "passive"))
    )
    (net (code "102") (name "VOUT") (class "Default")
      (node (ref "C1") (pin "1") (pintype "passive"))
      (node (ref "C10") (pin "1") (pinfunction "1_1") (pintype "passive"))
      (node (ref "C12") (pin "2") (pintype "passive"))
      (node (ref "Q4") (pin "S") (pinfunction "S_S") (pintype "passive"))
      (node (ref "Q6") (pin "S") (pinfunction "S_S") (pintype "passive"))
      (node (ref "R17") (pin "2") (pintype "passive"))
      (node (ref "R32") (pin "2") (pintype "passive"))
      (node (ref "R55") (pin "1") (pintype "passive"))
      (node (ref "R84") (pin "1") (pintype "passive"))
      (node (ref "U14") (pin "5") (pinfunction "vout_5") (pintype "passive"))
      (node (ref "U4") (pin "4") (pinfunction "OUT_4") (pintype "passive"))
    )
    (net (code "103") (name "VOUT_BF") (class "Default")
      (node (ref "Q1") (pin "S") (pinfunction "S_S") (pintype "passive"))
      (node (ref "Q8") (pin "S") (pinfunction "S_S") (pintype "passive"))
      (node (ref "R10") (pin "2") (pintype "passive"))
      (node (ref "R3") (pin "2") (pintype "passive"))
      (node (ref "R48") (pin "2") (pintype "passive"))
      (node (ref "R91") (pin "1") (pintype "passive"))
      (node (ref "U13") (pin "5") (pinfunction "vout_5") (pintype "passive"))
    )
    (net (code "104") (name "VTEST_OUT1") (class "Default")
      (node (ref "R34") (pin "2") (pintype "passive"))
      (node (ref "R38") (pin "1") (pintype "passive"))
      (node (ref "R94") (pin "1") (pintype "passive"))
      (node (ref "TP2") (pin "1") (pinfunction "TP_1") (pintype "passive"))
    )
    (net (code "105") (name "VTEST_OUT2") (class "Default")
      (node (ref "Q1") (pin "D") (pinfunction "D_D") (pintype "passive"))
      (node (ref "R49") (pin "2") (pintype "passive"))
      (node (ref "R50") (pin "1") (pintype "passive"))
      (node (ref "TP3") (pin "1") (pinfunction "TP_1") (pintype "passive"))
    )
    (net (code "106") (name "unconnected-(U1-COM0-Pad56)") (class "Default")
      (node (ref "U1") (pin "56") (pinfunction "COM0_56") (pintype "passive"))
    )
    (net (code "107") (name "unconnected-(U1-COM1-Pad55)") (class "Default")
      (node (ref "U1") (pin "55") (pinfunction "COM1_55") (pintype "passive"))
    )
    (net (code "108") (name "unconnected-(U1-COM2-Pad54)") (class "Default")
      (node (ref "U1") (pin "54") (pinfunction "COM2_54") (pintype "passive"))
    )
    (net (code "109") (name "unconnected-(U1-COM3-Pad53)") (class "Default")
      (node (ref "U1") (pin "53") (pinfunction "COM3_53") (pintype "passive"))
    )
    (net (code "110") (name "unconnected-(U1-COM4{slash}SEG0-Pad52)") (class "Default")
      (node (ref "U1") (pin "52") (pinfunction "COM4/SEG0_52") (pintype "passive"))
    )
    (net (code "111") (name "unconnected-(U1-COM5{slash}SEG1-Pad51)") (class "Default")
      (node (ref "U1") (pin "51") (pinfunction "COM5/SEG1_51") (pintype "passive"))
    )
    (net (code "112") (name "unconnected-(U1-COM6{slash}SEG2-Pad50)") (class "Default")
      (node (ref "U1") (pin "50") (pinfunction "COM6/SEG2_50") (pintype "passive"))
    )
    (net (code "113") (name "unconnected-(U1-COM7{slash}SEG3-Pad49)") (class "Default")
      (node (ref "U1") (pin "49") (pinfunction "COM7/SEG3_49") (pintype "passive"))
    )
    (net (code "114") (name "unconnected-(U1-P44{slash}SCL10-Pad5)") (class "Default")
      (node (ref "U1") (pin "5") (pinfunction "P44/SCL10_5") (pintype "passive"))
    )
    (net (code "115") (name "unconnected-(U1-P121{slash}X1-Pad15)") (class "Default")
      (node (ref "U1") (pin "15") (pinfunction "P121/X1_15") (pintype "passive"))
    )
    (net (code "116") (name "unconnected-(U1-P122{slash}X2{slash}EXCLK-Pad14)") (class "Default")
      (node (ref "U1") (pin "14") (pinfunction "P122/X2/EXCLK_14") (pintype "passive"))
    )
    (net (code "117") (name "unconnected-(U1-P125{slash}VL3-Pad26)") (class "Default")
      (node (ref "U1") (pin "26") (pinfunction "P125/VL3_26") (pintype "passive"))
    )
    (net (code "118") (name "unconnected-(U1-REGC-Pad16)") (class "Default")
      (node (ref "U1") (pin "16") (pinfunction "REGC_16") (pintype "passive"))
    )
    (net (code "119") (name "unconnected-(U1-VL1-Pad23)") (class "Default")
      (node (ref "U1") (pin "23") (pinfunction "VL1_23") (pintype "passive"))
    )
    (net (code "120") (name "unconnected-(U1-VL2-Pad24)") (class "Default")
      (node (ref "U1") (pin "24") (pinfunction "VL2_24") (pintype "passive"))
    )
    (net (code "121") (name "unconnected-(U1-VL4-Pad25)") (class "Default")
      (node (ref "U1") (pin "25") (pinfunction "VL4_25") (pintype "passive"))
    )
  )
)
